# DC_DC_Buck.net
KiCad netlist of a schematic drawn in Altium Designer
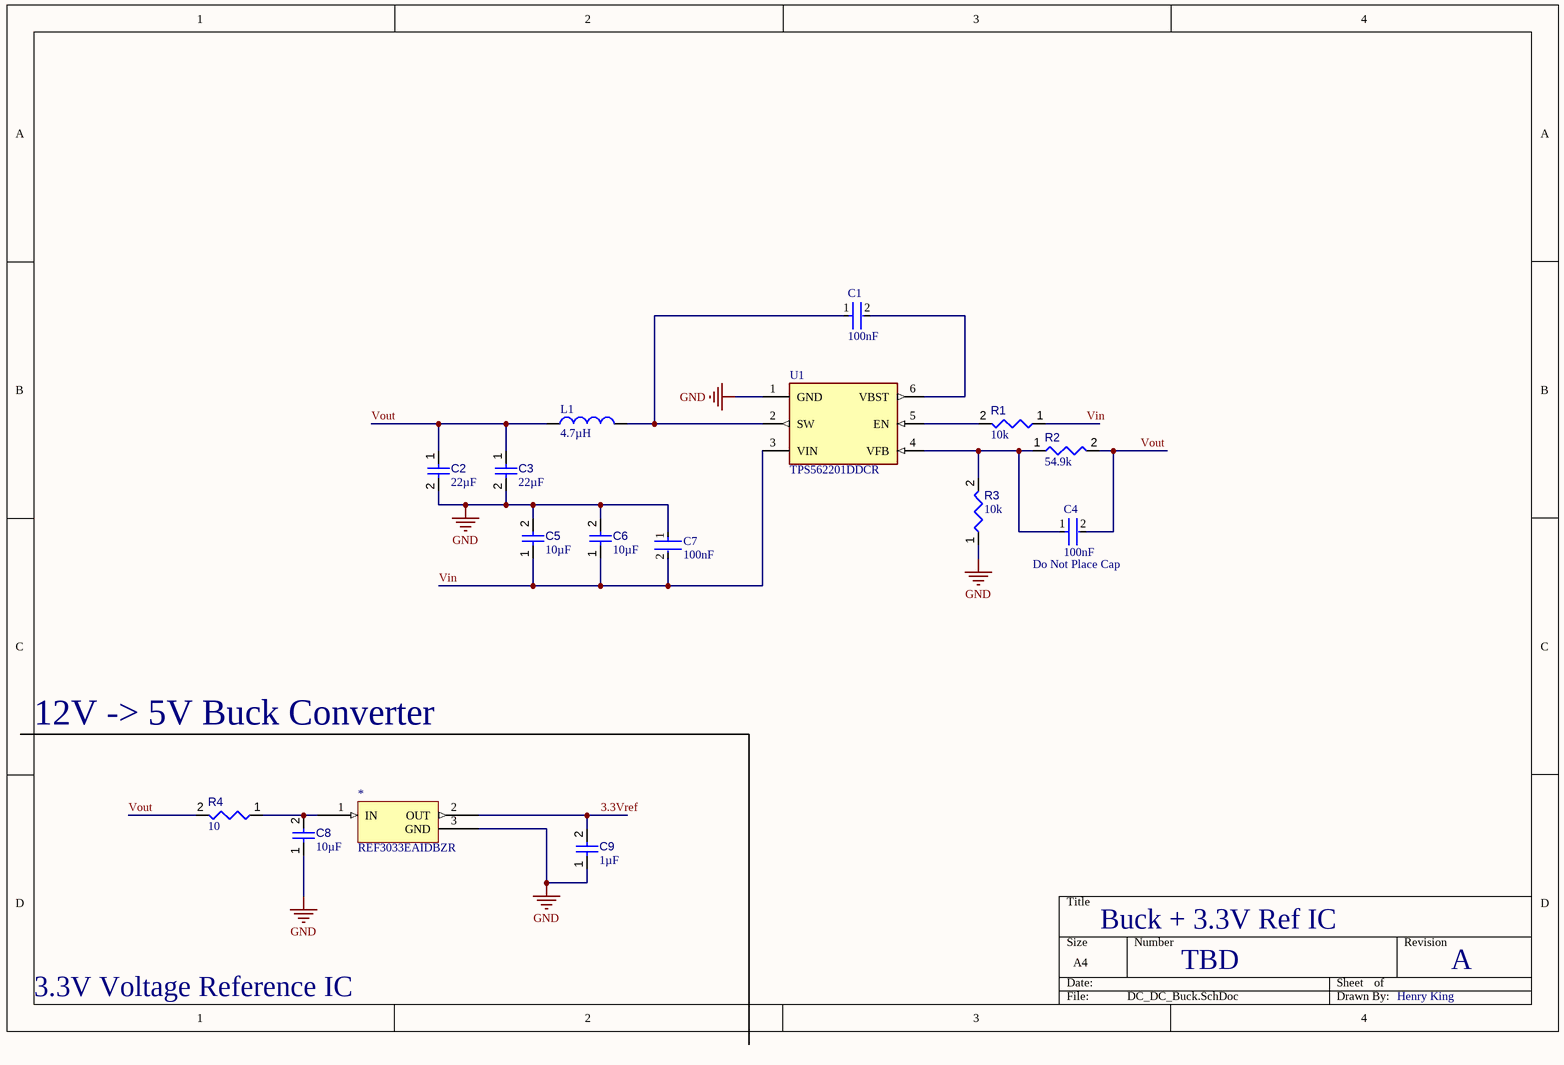
[diagram p0: DC_DC_Buck.SchDoc]

(export (version "E")
  (design (tool "Eeschema 10.0.6"))
  (components
    (comp (ref "*")
      (value "REF3033EAIDBZR")
      (footprint "SOT95P235X112-3N")
      (description "15 ppm°/C drift, 27uA Iq in SOT-23-3 package series voltage reference 3-SOT-23 -40 to 125")
      (libsource (lib "Henry King") (part "REF3033EAIDBZR-Symbol-1"))
    )
    (comp (ref "C1")
      (value "100nF")
      (footprint "FP-GRM188-0_1-e0_2_0_5-IPC_B")
      (description "100V 100nF X7R ±10% 0603 Multilayer Ceramic Capacitors MLCC - SMD/SMT ROHS")
      (fields (field (name "TOLERANCE") "10%") (field (name "Comment") "Capacitor 100nF 0603"))
      (libsource (lib "Henry King") (part "11868f565c42a9108669ba33697ecf6"))
    )
    (comp (ref "C2")
      (value "22µF")
      (footprint "FP-1206-L_3_2_0_3-W_1_6_0-IPC_B")
      (description "CAP CER 22UF 25V X5R 1206 / High Value Multilayer Ceramic Capacitors (High dielectric type)")
      (fields (field (name "TOLERANCE") "20%") (field (name "Comment") "22uf Capacitor 1206"))
      (libsource (lib "Henry King") (part "CAP-NP-2"))
    )
    (comp (ref "C3")
      (value "22µF")
      (footprint "FP-1206-L_3_2_0_3-W_1_6_0-IPC_B")
      (description "CAP CER 22UF 25V X5R 1206 / High Value Multilayer Ceramic Capacitors (High dielectric type)")
      (fields (field (name "TOLERANCE") "20%") (field (name "Comment") "22uf Capacitor 1206"))
      (libsource (lib "Henry King") (part "CAP-NP-2"))
    )
    (comp (ref "C4")
      (value "100nF")
      (footprint "FP-GRM188-0_1-e0_2_0_5-IPC_B")
      (description "100V 100nF X7R ±10% 0603 Multilayer Ceramic Capacitors MLCC - SMD/SMT ROHS")
      (fields (field (name "TOLERANCE") "10%") (field (name "Comment") "Capacitor 100nF 0603"))
      (libsource (lib "Henry King") (part "11868f565c42a9108669ba33697ecf6"))
    )
    (comp (ref "C5")
      (value "10µF")
      (footprint "CAPC2012X135N")
      (description "16V 10uF X7R 卤10% 0805 Multilayer Ceramic Capacitors MLCC - SMD/SMT ROHS")
      (fields (field (name "TOLERANCE") "10%") (field (name "Comment") "CL21B106KOQNNNE"))
      (libsource (lib "Henry King") (part "CAP-NP-2"))
    )
    (comp (ref "C6")
      (value "10µF")
      (footprint "CAPC2012X135N")
      (description "16V 10uF X7R 卤10% 0805 Multilayer Ceramic Capacitors MLCC - SMD/SMT ROHS")
      (fields (field (name "TOLERANCE") "10%") (field (name "Comment") "CL21B106KOQNNNE"))
      (libsource (lib "Henry King") (part "CAP-NP-2"))
    )
    (comp (ref "C7")
      (value "100nF")
      (footprint "FP-GRM188-0_1-e0_2_0_5-IPC_B")
      (description "100V 100nF X7R ±10% 0603 Multilayer Ceramic Capacitors MLCC - SMD/SMT ROHS")
      (fields (field (name "TOLERANCE") "10%") (field (name "Comment") "Capacitor 100nF 0603"))
      (libsource (lib "Henry King") (part "11868f565c42a9108669ba33697ecf6"))
    )
    (comp (ref "C8")
      (value "10µF")
      (footprint "CAPC2012X135N")
      (description "16V 10uF X7R 卤10% 0805 Multilayer Ceramic Capacitors MLCC - SMD/SMT ROHS")
      (fields (field (name "TOLERANCE") "10%") (field (name "Comment") "CL21B106KOQNNNE"))
      (libsource (lib "Henry King") (part "CAP-NP-2"))
    )
    (comp (ref "C9")
      (value "1µF")
      (footprint "CAPC1608X90X35ML15T15")
      (description "Chip Capacitor, 1 uF, +/- 10%, 16 V, 0603 (1608 Metric)")
      (fields (field (name "TOLERANCE") "10%") (field (name "Comment") "Capacitor 1uF +/- 10% 16V 0603"))
      (libsource (lib "Henry King") (part "CAP-NP-2"))
    )
    (comp (ref "L1")
      (value "4.7µH")
      (footprint "INDM5252X300N")
      (description "Inductor Power Wirewound 4.7uH 20% 100KHz Ferrite 3.5A 77.5mOhm DCR")
      (fields (field (name "TOLERANCE") "20%") (field (name "Comment") "LMLP0506M4R7DTAS"))
      (libsource (lib "Henry King") (part "IND-2"))
    )
    (comp (ref "R1")
      (value "10k")
      (footprint "RESC1608X55X25ML10T15")
      (description "Chip Resistor, 10 KOhm, +/- 1%, 01 W, -55 to 155 degC, 0603 (1608 Metric)")
      (fields (field (name "POWER") "100mW") (field (name "TOLERANCE") "1%"))
      (libsource (lib "Henry King") (part "RES-2"))
    )
    (comp (ref "R2")
      (value "54.9k")
      (footprint "FP-RMCF0603-IPC_B")
      (description "Res Thick Film 0603 54.9K Ohm 1% 0.1W(1/10W) ±100ppm/C Pad SMD Automotive T/R")
      (fields (field (name "TOLERANCE") "1%") (field (name "Comment") "54.9kohm 0603 Resistor"))
      (libsource (lib "Henry King") (part "RES-2"))
    )
    (comp (ref "R3")
      (value "10k")
      (footprint "RESC1608X55X25ML10T15")
      (description "Chip Resistor, 10 KOhm, +/- 1%, 01 W, -55 to 155 degC, 0603 (1608 Metric)")
      (fields (field (name "POWER") "100mW") (field (name "TOLERANCE") "1%"))
      (libsource (lib "Henry King") (part "RES-2"))
    )
    (comp (ref "R4")
      (value "10")
      (footprint "RESC0402(1005)_L")
      (description "Chip Resistor, 10 Ohms, +/-1 %, 63 mW, -55 to 155 degC, 0402")
      (fields (field (name "TOLERANCE") "1%") (field (name "POWER") "63mW"))
      (libsource (lib "Henry King") (part "RES-2"))
    )
    (comp (ref "U1")
      (value "TPS562201DDCR")
      (footprint "FP-DDC0006A-MFG")
      (description "Buck 580KHz Adjustable SOT-23-THIN SMD mount 1.1mm(height)")
      (libsource (lib "Henry King") (part "957e164956730ea4bf6293280af19fc"))
    )
  )
  (nets
    (net (code "1") (name "/3.3Vref") (class "Default")
      (node (ref "*") (pin "2") (pinfunction "OUT_2") (pintype "output"))
      (node (ref "C9") (pin "2") (pinfunction "2_2") (pintype "passive"))
    )
    (net (code "2") (name "/Vin") (class "Default")
      (node (ref "C5") (pin "1") (pinfunction "1_1") (pintype "passive"))
      (node (ref "C6") (pin "1") (pinfunction "1_1") (pintype "passive"))
      (node (ref "C7") (pin "2") (pinfunction "2_2") (pintype "passive"))
      (node (ref "R1") (pin "1") (pinfunction "1_1") (pintype "passive"))
      (node (ref "U1") (pin "3") (pinfunction "VIN_3") (pintype "power_in"))
    )
    (net (code "3") (name "/Vout") (class "Default")
      (node (ref "C2") (pin "1") (pinfunction "1_1") (pintype "passive"))
      (node (ref "C3") (pin "1") (pinfunction "1_1") (pintype "passive"))
      (node (ref "C4") (pin "2") (pinfunction "2_2") (pintype "passive"))
      (node (ref "L1") (pin "1") (pinfunction "1_1") (pintype "passive"))
      (node (ref "R2") (pin "2") (pinfunction "2_2") (pintype "passive"))
      (node (ref "R4") (pin "2") (pinfunction "2_2") (pintype "passive"))
    )
    (net (code "4") (name "GND") (class "Default")
      (node (ref "*") (pin "3") (pinfunction "GND_3") (pintype "passive"))
      (node (ref "C2") (pin "2") (pinfunction "2_2") (pintype "passive"))
      (node (ref "C3") (pin "2") (pinfunction "2_2") (pintype "passive"))
      (node (ref "C5") (pin "2") (pinfunction "2_2") (pintype "passive"))
      (node (ref "C6") (pin "2") (pinfunction "2_2") (pintype "passive"))
      (node (ref "C7") (pin "1") (pinfunction "1_1") (pintype "passive"))
      (node (ref "C8") (pin "1") (pinfunction "1_1") (pintype "passive"))
      (node (ref "C9") (pin "1") (pinfunction "1_1") (pintype "passive"))
      (node (ref "R3") (pin "1") (pinfunction "1_1") (pintype "passive"))
      (node (ref "U1") (pin "1") (pinfunction "GND_1") (pintype "passive"))
    )
    (net (code "5") (name "Net-(*-IN)") (class "Default")
      (node (ref "*") (pin "1") (pinfunction "IN_1") (pintype "input"))
      (node (ref "C8") (pin "2") (pinfunction "2_2") (pintype "passive"))
      (node (ref "R4") (pin "1") (pinfunction "1_1") (pintype "passive"))
    )
    (net (code "6") (name "Net-(U1-EN)") (class "Default")
      (node (ref "R1") (pin "2") (pinfunction "2_2") (pintype "passive"))
      (node (ref "U1") (pin "5") (pinfunction "EN_5") (pintype "input"))
    )
    (net (code "7") (name "Net-(U1-SW)") (class "Default")
      (node (ref "C1") (pin "1") (pinfunction "1_1") (pintype "passive"))
      (node (ref "L1") (pin "2") (pinfunction "2_2") (pintype "passive"))
      (node (ref "U1") (pin "2") (pinfunction "SW_2") (pintype "output"))
    )
    (net (code "8") (name "Net-(U1-VBST)") (class "Default")
      (node (ref "C1") (pin "2") (pinfunction "2_2") (pintype "passive"))
      (node (ref "U1") (pin "6") (pinfunction "VBST_6") (pintype "output"))
    )
    (net (code "9") (name "Net-(U1-VFB)") (class "Default")
      (node (ref "C4") (pin "1") (pinfunction "1_1") (pintype "passive"))
      (node (ref "R2") (pin "1") (pinfunction "1_1") (pintype "passive"))
      (node (ref "R3") (pin "2") (pinfunction "2_2") (pintype "passive"))
      (node (ref "U1") (pin "4") (pinfunction "VFB_4") (pintype "input"))
    )
  )
)
